# BusPirate-v5_0-SSOP.net
KiCad netlist of a schematic drawn in EAGLE
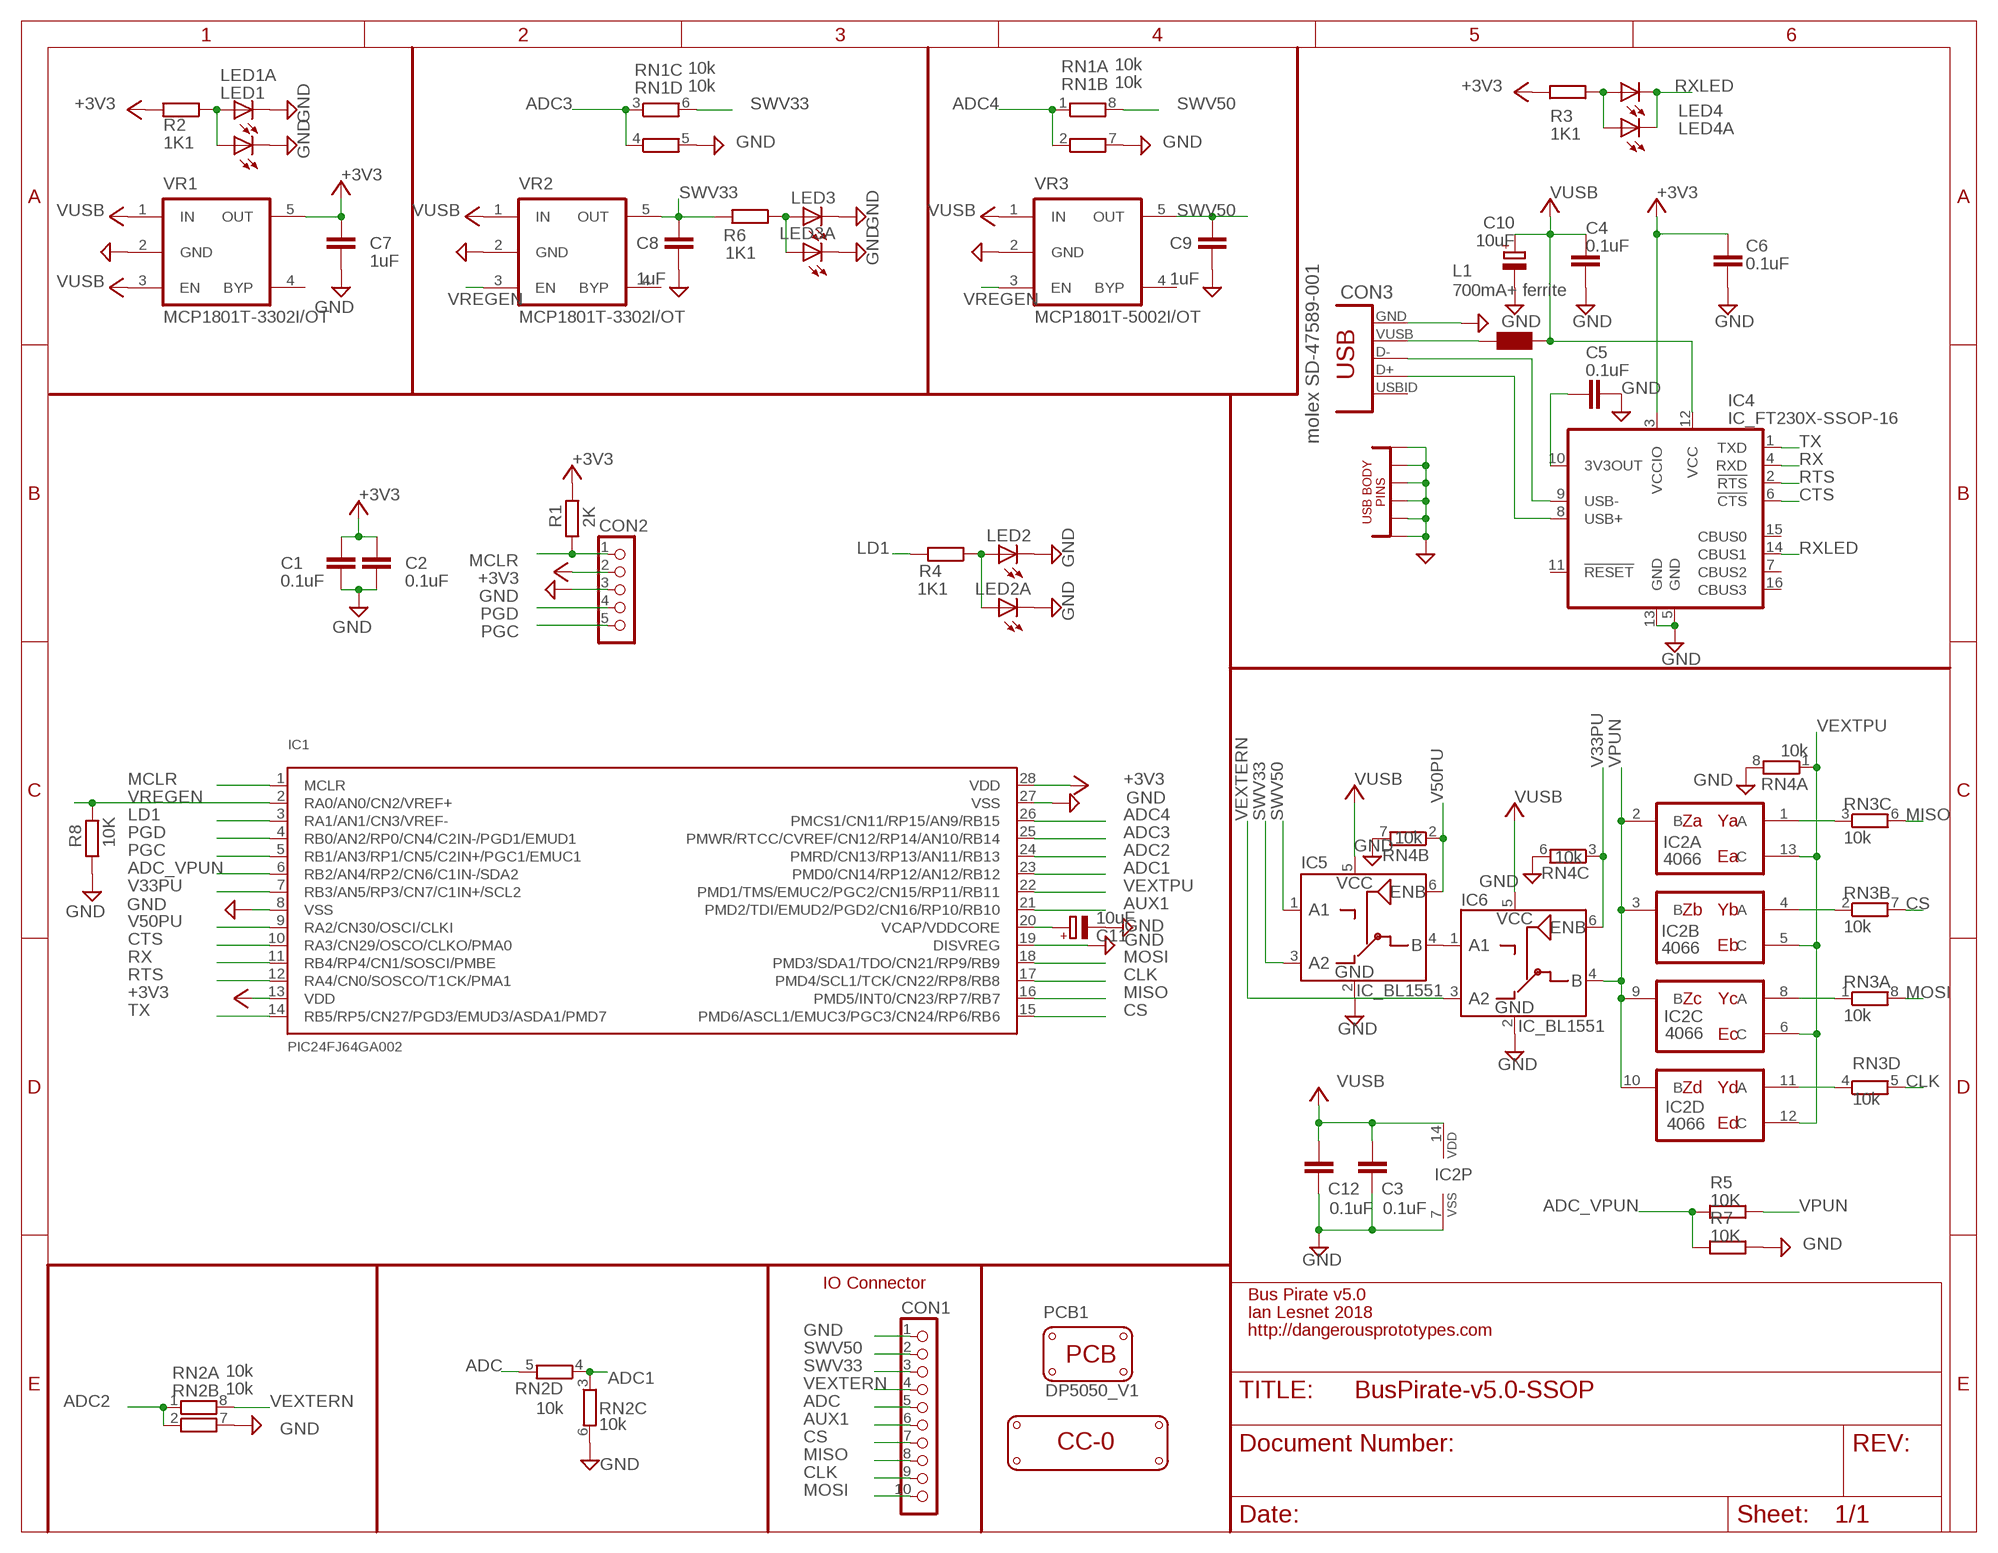
[diagram p0: schematic, sheet 1]

(export (version "E")
  (design (tool "Eeschema 10.0.6"))
  (components
    (comp (ref "C1")
      (value "0.1uF")
      (footprint "eagle-import:C603")
      (libsource (lib "eagle-import") (part "CAPC603"))
    )
    (comp (ref "C2")
      (value "0.1uF")
      (footprint "eagle-import:C603")
      (libsource (lib "eagle-import") (part "CAPC603"))
    )
    (comp (ref "C3")
      (value "0.1uF")
      (footprint "eagle-import:C603")
      (libsource (lib "eagle-import") (part "CAPC603"))
    )
    (comp (ref "C4")
      (value "0.1uF")
      (footprint "eagle-import:C603")
      (libsource (lib "eagle-import") (part "CAPC603"))
    )
    (comp (ref "C5")
      (value "0.1uF")
      (footprint "eagle-import:C603")
      (libsource (lib "eagle-import") (part "CAPC603"))
    )
    (comp (ref "C6")
      (value "0.1uF")
      (footprint "eagle-import:C603")
      (libsource (lib "eagle-import") (part "CAPC603"))
    )
    (comp (ref "C7")
      (value "1uF")
      (footprint "eagle-import:C603")
      (libsource (lib "eagle-import") (part "CAPC603"))
    )
    (comp (ref "C8")
      (value "1uF")
      (footprint "eagle-import:C603")
      (libsource (lib "eagle-import") (part "CAPC603"))
    )
    (comp (ref "C9")
      (value "1uF")
      (footprint "eagle-import:C603")
      (libsource (lib "eagle-import") (part "CAPC603"))
    )
    (comp (ref "C10")
      (value "10uF")
      (footprint "eagle-import:SMC_A")
      (libsource (lib "eagle-import") (part "CPOL-EUSMCA"))
    )
    (comp (ref "C11")
      (value "10uF")
      (footprint "eagle-import:SMC_A")
      (libsource (lib "eagle-import") (part "CPOL-EUSMCA"))
    )
    (comp (ref "C12")
      (value "0.1uF")
      (footprint "eagle-import:C603")
      (libsource (lib "eagle-import") (part "CAPC603"))
    )
    (comp (ref "CON1")
      (value "CON_HEADER_1X10-RIGHT_ANGLED_PTH_SHROUDED")
      (footprint "eagle-import:M1X10_MALE_RIGHT_ANGLES_PTH_SHROUDED")
      (libsource (lib "eagle-import") (part "CON_HEADER_1X10-RIGHT_ANGLED_PTH_SHROUDED"))
    )
    (comp (ref "CON2")
      (value "CON_HEADER_1X05-PTH")
      (footprint "eagle-import:M1X5")
      (libsource (lib "eagle-import") (part "CON_HEADER_1X05-PTH"))
    )
    (comp (ref "CON3")
      (value "molex SD-47589-001")
      (footprint "eagle-import:CON_USB_MICRO-B-2-SD-47589-001")
      (libsource (lib "eagle-import") (part "CON-USB-F-MICRO-B-2"))
    )
    (comp (ref "IC1")
      (value "PIC24FJ64GA002")
      (footprint "eagle-import:SSOP28")
      (libsource (lib "eagle-import") (part "PIC24FJ64GA002"))
    )
    (comp (ref "IC2")
      (value "4066")
      (footprint "eagle-import:TSSOP14")
      (libsource (lib "eagle-import") (part "4066"))
    )
    (comp (ref "IC4")
      (value "IC_FT230X-SSOP-16")
      (footprint "eagle-import:SSOP-16-FTDI")
      (libsource (lib "eagle-import") (part "IC_FT230X-SSOP-16"))
    )
    (comp (ref "IC5")
      (value "IC_BL1551")
      (footprint "eagle-import:SC-70-6")
      (libsource (lib "eagle-import") (part "IC_BL1551"))
    )
    (comp (ref "IC6")
      (value "IC_BL1551")
      (footprint "eagle-import:SC-70-6")
      (libsource (lib "eagle-import") (part "IC_BL1551"))
    )
    (comp (ref "L1")
      (value "700mA+ ferrite")
      (footprint "eagle-import:WE-KI_0805_B")
      (libsource (lib "eagle-import") (part "WE-KIL_0805"))
    )
    (comp (ref "LED1")
      (value "LED-0805")
      (footprint "eagle-import:LED-805")
      (libsource (lib "eagle-import") (part "LED-0805"))
    )
    (comp (ref "LED1A")
      (value "LED-0805")
      (footprint "eagle-import:LED-805")
      (libsource (lib "eagle-import") (part "LED-0805"))
    )
    (comp (ref "LED2")
      (value "LED-0805")
      (footprint "eagle-import:LED-805")
      (libsource (lib "eagle-import") (part "LED-0805"))
    )
    (comp (ref "LED2A")
      (value "LED-0805")
      (footprint "eagle-import:LED-805")
      (libsource (lib "eagle-import") (part "LED-0805"))
    )
    (comp (ref "LED3")
      (value "LED-0805")
      (footprint "eagle-import:LED-805")
      (libsource (lib "eagle-import") (part "LED-0805"))
    )
    (comp (ref "LED3A")
      (value "LED-0805")
      (footprint "eagle-import:LED-805")
      (libsource (lib "eagle-import") (part "LED-0805"))
    )
    (comp (ref "LED4")
      (value "LED-0805")
      (footprint "eagle-import:LED-805")
      (libsource (lib "eagle-import") (part "LED-0805"))
    )
    (comp (ref "LED4A")
      (value "LED-0805")
      (footprint "eagle-import:LED-805")
      (libsource (lib "eagle-import") (part "LED-0805"))
    )
    (comp (ref "LOGO1")
      (value "LOGO_CC-0")
      (footprint "eagle-import:LOGO_CC-0")
      (libsource (lib "eagle-import") (part "LOGO_CC-0"))
    )
    (comp (ref "PCB1")
      (value "PCB_DP_SQUARE-5X5")
      (footprint "eagle-import:DP5050_V1")
      (libsource (lib "eagle-import") (part "PCB_DP_SQUARE-5X5"))
    )
    (comp (ref "R1")
      (value "2K")
      (footprint "eagle-import:R603")
      (libsource (lib "eagle-import") (part "RESISTORR603"))
    )
    (comp (ref "R2")
      (value "1K1")
      (footprint "eagle-import:R603")
      (libsource (lib "eagle-import") (part "RESISTORR603"))
    )
    (comp (ref "R3")
      (value "1K1")
      (footprint "eagle-import:R603")
      (libsource (lib "eagle-import") (part "RESISTORR603"))
    )
    (comp (ref "R4")
      (value "1K1")
      (footprint "eagle-import:R603")
      (libsource (lib "eagle-import") (part "RESISTORR603"))
    )
    (comp (ref "R5")
      (value "10K")
      (footprint "eagle-import:R603")
      (libsource (lib "eagle-import") (part "RESISTORR603"))
    )
    (comp (ref "R6")
      (value "1K1")
      (footprint "eagle-import:R603")
      (libsource (lib "eagle-import") (part "RESISTORR603"))
    )
    (comp (ref "R7")
      (value "10K")
      (footprint "eagle-import:R603")
      (libsource (lib "eagle-import") (part "RESISTORR603"))
    )
    (comp (ref "R8")
      (value "10K")
      (footprint "eagle-import:R603")
      (libsource (lib "eagle-import") (part "RESISTORR603"))
    )
    (comp (ref "RN1")
      (value "10k")
      (footprint "eagle-import:RN8P-4R-CRA06S")
      (libsource (lib "eagle-import") (part "RNETWORK"))
    )
    (comp (ref "RN2")
      (value "10k")
      (footprint "eagle-import:RN8P-4R-CRA06S")
      (libsource (lib "eagle-import") (part "RNETWORK"))
    )
    (comp (ref "RN3")
      (value "10k")
      (footprint "eagle-import:RN8P-4R-CRA06S")
      (libsource (lib "eagle-import") (part "RNETWORK"))
    )
    (comp (ref "RN4")
      (value "10k")
      (footprint "eagle-import:RN8P-4R-CRA06S")
      (libsource (lib "eagle-import") (part "RNETWORK"))
    )
    (comp (ref "VR1")
      (value "MCP1801T-3302I/OT")
      (footprint "eagle-import:SOT-23-5")
      (libsource (lib "eagle-import") (part "MIC5205"))
    )
    (comp (ref "VR2")
      (value "MCP1801T-3302I/OT")
      (footprint "eagle-import:SOT-23-5")
      (libsource (lib "eagle-import") (part "MIC5205"))
    )
    (comp (ref "VR3")
      (value "MCP1801T-5002I/OT")
      (footprint "eagle-import:SOT-23-5")
      (libsource (lib "eagle-import") (part "MIC5205"))
    )
  )
  (nets
    (net (code "1") (name "/ADC") (class "Default")
      (node (ref "CON1") (pin "5") (pinfunction "5_5") (pintype "passive"))
      (node (ref "RN2") (pin "5") (pinfunction "2_5") (pintype "passive"))
    )
    (net (code "2") (name "/ADC1") (class "Default")
      (node (ref "IC1") (pin "23") (pinfunction "PMD0/CN14/RP12/AN12/RB12_23") (pintype "bidirectional"))
      (node (ref "RN2") (pin "3") (pinfunction "1_3") (pintype "passive"))
      (node (ref "RN2") (pin "4") (pinfunction "1_4") (pintype "passive"))
    )
    (net (code "3") (name "/ADC2") (class "Default")
      (node (ref "IC1") (pin "24") (pinfunction "PMRD/CN13/RP13/AN11/RB13_24") (pintype "bidirectional"))
      (node (ref "RN2") (pin "1") (pinfunction "1_1") (pintype "passive"))
      (node (ref "RN2") (pin "2") (pinfunction "1_2") (pintype "passive"))
    )
    (net (code "4") (name "/ADC3") (class "Default")
      (node (ref "IC1") (pin "25") (pinfunction "PMWR/RTCC/CVREF/CN12/RP14/AN10/RB14_25") (pintype "bidirectional"))
      (node (ref "RN1") (pin "3") (pinfunction "1_3") (pintype "passive"))
      (node (ref "RN1") (pin "4") (pinfunction "1_4") (pintype "passive"))
    )
    (net (code "5") (name "/ADC4") (class "Default")
      (node (ref "IC1") (pin "26") (pinfunction "PMCS1/CN11/RP15/AN9/RB15_26") (pintype "bidirectional"))
      (node (ref "RN1") (pin "1") (pinfunction "1_1") (pintype "passive"))
      (node (ref "RN1") (pin "2") (pinfunction "1_2") (pintype "passive"))
    )
    (net (code "6") (name "/ADC_VPUN") (class "Default")
      (node (ref "IC1") (pin "6") (pinfunction "RB2/AN4/RP2/CN6/C1IN-/SDA2_6") (pintype "bidirectional"))
      (node (ref "R5") (pin "2") (pinfunction "2_2") (pintype "passive"))
      (node (ref "R7") (pin "2") (pinfunction "2_2") (pintype "passive"))
    )
    (net (code "7") (name "/AUX1") (class "Default")
      (node (ref "CON1") (pin "6") (pinfunction "6_6") (pintype "passive"))
      (node (ref "IC1") (pin "21") (pinfunction "PMD2/TDI/EMUD2/PGD2/CN16/RP10/RB10_21") (pintype "bidirectional"))
    )
    (net (code "8") (name "/CLK") (class "Default")
      (node (ref "CON1") (pin "9") (pinfunction "9_9") (pintype "passive"))
      (node (ref "IC1") (pin "17") (pinfunction "PMD4/SCL1/TCK/CN22/RP8/RB8_17") (pintype "bidirectional"))
      (node (ref "RN3") (pin "5") (pinfunction "2_5") (pintype "passive"))
    )
    (net (code "9") (name "/CS") (class "Default")
      (node (ref "CON1") (pin "7") (pinfunction "7_7") (pintype "passive"))
      (node (ref "IC1") (pin "15") (pinfunction "PMD6/ASCL1/EMUC3/PGC3/CN24/RP6/RB6_15") (pintype "bidirectional"))
      (node (ref "RN3") (pin "7") (pinfunction "2_7") (pintype "passive"))
    )
    (net (code "10") (name "/CTS") (class "Default")
      (node (ref "IC1") (pin "10") (pinfunction "RA3/CN29/OSCO/CLKO/PMA0_10") (pintype "bidirectional"))
      (node (ref "IC4") (pin "6") (pinfunction "~{CTS}_6") (pintype "bidirectional"))
    )
    (net (code "11") (name "/LD1") (class "Default")
      (node (ref "IC1") (pin "3") (pinfunction "RA1/AN1/CN3/VREF-_3") (pintype "bidirectional"))
      (node (ref "R4") (pin "2") (pinfunction "2_2") (pintype "passive"))
    )
    (net (code "12") (name "/MCLR") (class "Default")
      (node (ref "CON2") (pin "1") (pinfunction "1_1") (pintype "bidirectional"))
      (node (ref "IC1") (pin "1") (pinfunction "MCLR_1") (pintype "input"))
      (node (ref "R1") (pin "1") (pinfunction "1_1") (pintype "passive"))
    )
    (net (code "13") (name "/MISO") (class "Default")
      (node (ref "CON1") (pin "8") (pinfunction "8_8") (pintype "passive"))
      (node (ref "IC1") (pin "16") (pinfunction "PMD5/INT0/CN23/RP7/RB7_16") (pintype "bidirectional"))
      (node (ref "RN3") (pin "6") (pinfunction "2_6") (pintype "passive"))
    )
    (net (code "14") (name "/MOSI") (class "Default")
      (node (ref "CON1") (pin "10") (pinfunction "10_10") (pintype "passive"))
      (node (ref "IC1") (pin "18") (pinfunction "PMD3/SDA1/TDO/CN21/RP9/RB9_18") (pintype "bidirectional"))
      (node (ref "RN3") (pin "8") (pinfunction "2_8") (pintype "passive"))
    )
    (net (code "15") (name "/PGC") (class "Default")
      (node (ref "CON2") (pin "5") (pinfunction "5_5") (pintype "bidirectional"))
      (node (ref "IC1") (pin "5") (pinfunction "RB1/AN3/RP1/CN5/C2IN+/PGC1/EMUC1_5") (pintype "bidirectional"))
    )
    (net (code "16") (name "/PGD") (class "Default")
      (node (ref "CON2") (pin "4") (pinfunction "4_4") (pintype "bidirectional"))
      (node (ref "IC1") (pin "4") (pinfunction "RB0/AN2/RP0/CN4/C2IN-/PGD1/EMUD1_4") (pintype "bidirectional"))
    )
    (net (code "17") (name "/RTS") (class "Default")
      (node (ref "IC1") (pin "12") (pinfunction "RA4/CN0/SOSCO/T1CK/PMA1_12") (pintype "bidirectional"))
      (node (ref "IC4") (pin "2") (pinfunction "~{RTS}_2") (pintype "bidirectional"))
    )
    (net (code "18") (name "/RX") (class "Default")
      (node (ref "IC1") (pin "11") (pinfunction "RB4/RP4/CN1/SOSCI/PMBE_11") (pintype "bidirectional"))
      (node (ref "IC4") (pin "4") (pinfunction "RXD_4") (pintype "input"))
    )
    (net (code "19") (name "/RXLED") (class "Default")
      (node (ref "IC4") (pin "14") (pinfunction "CBUS1_14") (pintype "bidirectional"))
      (node (ref "LED4") (pin "C") (pinfunction "C_C") (pintype "passive"))
      (node (ref "LED4A") (pin "C") (pinfunction "C_C") (pintype "passive"))
    )
    (net (code "20") (name "/SWV33") (class "Default")
      (node (ref "C8") (pin "1") (pinfunction "1_1") (pintype "passive"))
      (node (ref "CON1") (pin "3") (pinfunction "3_3") (pintype "passive"))
      (node (ref "IC5") (pin "3") (pinfunction "A2_3") (pintype "input"))
      (node (ref "R6") (pin "2") (pinfunction "2_2") (pintype "passive"))
      (node (ref "RN1") (pin "6") (pinfunction "2_6") (pintype "passive"))
      (node (ref "VR2") (pin "5") (pinfunction "OUT_5") (pintype "bidirectional"))
    )
    (net (code "21") (name "/SWV50") (class "Default")
      (node (ref "C9") (pin "1") (pinfunction "1_1") (pintype "passive"))
      (node (ref "CON1") (pin "2") (pinfunction "2_2") (pintype "passive"))
      (node (ref "IC5") (pin "1") (pinfunction "A1_1") (pintype "input"))
      (node (ref "RN1") (pin "8") (pinfunction "2_8") (pintype "passive"))
      (node (ref "VR3") (pin "5") (pinfunction "OUT_5") (pintype "bidirectional"))
    )
    (net (code "22") (name "/TX") (class "Default")
      (node (ref "IC1") (pin "14") (pinfunction "RB5/RP5/CN27/PGD3/EMUD3/ASDA1/PMD7_14") (pintype "bidirectional"))
      (node (ref "IC4") (pin "1") (pinfunction "TXD_1") (pintype "output"))
    )
    (net (code "23") (name "/V33PU") (class "Default")
      (node (ref "IC1") (pin "7") (pinfunction "RB3/AN5/RP3/CN7/C1IN+/SCL2_7") (pintype "bidirectional"))
      (node (ref "IC6") (pin "6") (pinfunction "ENB_6") (pintype "input"))
      (node (ref "RN4") (pin "3") (pinfunction "1_3") (pintype "passive"))
    )
    (net (code "24") (name "/V50PU") (class "Default")
      (node (ref "IC1") (pin "9") (pinfunction "RA2/CN30/OSCI/CLKI_9") (pintype "bidirectional"))
      (node (ref "IC5") (pin "6") (pinfunction "ENB_6") (pintype "input"))
      (node (ref "RN4") (pin "2") (pinfunction "1_2") (pintype "passive"))
    )
    (net (code "25") (name "/VEXTERN") (class "Default")
      (node (ref "CON1") (pin "4") (pinfunction "4_4") (pintype "passive"))
      (node (ref "IC6") (pin "3") (pinfunction "A2_3") (pintype "input"))
      (node (ref "RN2") (pin "8") (pinfunction "2_8") (pintype "passive"))
    )
    (net (code "26") (name "/VEXTPU") (class "Default")
      (node (ref "IC1") (pin "22") (pinfunction "PMD1/TMS/EMUC2/PGC2/CN15/RP11/RB11_22") (pintype "bidirectional"))
      (node (ref "IC2") (pin "12") (pinfunction "C_12") (pintype "input"))
      (node (ref "IC2") (pin "13") (pinfunction "C_13") (pintype "input"))
      (node (ref "IC2") (pin "5") (pinfunction "C_5") (pintype "input"))
      (node (ref "IC2") (pin "6") (pinfunction "C_6") (pintype "input"))
      (node (ref "RN4") (pin "1") (pinfunction "1_1") (pintype "passive"))
    )
    (net (code "27") (name "/VPUN") (class "Default")
      (node (ref "IC2") (pin "10") (pinfunction "B_10") (pintype "tri_state"))
      (node (ref "IC2") (pin "2") (pinfunction "B_2") (pintype "tri_state"))
      (node (ref "IC2") (pin "3") (pinfunction "B_3") (pintype "tri_state"))
      (node (ref "IC2") (pin "9") (pinfunction "B_9") (pintype "tri_state"))
      (node (ref "IC6") (pin "4") (pinfunction "B_4") (pintype "output"))
      (node (ref "R5") (pin "1") (pinfunction "1_1") (pintype "passive"))
    )
    (net (code "28") (name "/VREGEN") (class "Default")
      (node (ref "IC1") (pin "2") (pinfunction "RA0/AN0/CN2/VREF+_2") (pintype "bidirectional"))
      (node (ref "R8") (pin "2") (pinfunction "2_2") (pintype "passive"))
      (node (ref "VR2") (pin "3") (pinfunction "EN_3") (pintype "bidirectional"))
      (node (ref "VR3") (pin "3") (pinfunction "EN_3") (pintype "bidirectional"))
    )
    (net (code "29") (name "GND") (class "Default")
      (node (ref "C1") (pin "2") (pinfunction "2_2") (pintype "passive"))
      (node (ref "C10") (pin "-") (pinfunction "-_-") (pintype "passive"))
      (node (ref "C11") (pin "-") (pinfunction "-_-") (pintype "passive"))
      (node (ref "C12") (pin "2") (pinfunction "2_2") (pintype "passive"))
      (node (ref "C2") (pin "2") (pinfunction "2_2") (pintype "passive"))
      (node (ref "C3") (pin "2") (pinfunction "2_2") (pintype "passive"))
      (node (ref "C4") (pin "2") (pinfunction "2_2") (pintype "passive"))
      (node (ref "C5") (pin "2") (pinfunction "2_2") (pintype "passive"))
      (node (ref "C6") (pin "2") (pinfunction "2_2") (pintype "passive"))
      (node (ref "C7") (pin "2") (pinfunction "2_2") (pintype "passive"))
      (node (ref "C8") (pin "2") (pinfunction "2_2") (pintype "passive"))
      (node (ref "C9") (pin "2") (pinfunction "2_2") (pintype "passive"))
      (node (ref "CON1") (pin "1") (pinfunction "1_1") (pintype "passive"))
      (node (ref "CON2") (pin "3") (pinfunction "3_3") (pintype "bidirectional"))
      (node (ref "CON3") (pin "BODY@1") (pinfunction "P$1_BODY@1") (pintype "passive"))
      (node (ref "CON3") (pin "BODY@10") (pinfunction "P$6_BODY@10") (pintype "passive"))
      (node (ref "CON3") (pin "BODY@2") (pinfunction "P$1_BODY@2") (pintype "passive"))
      (node (ref "CON3") (pin "BODY@3") (pinfunction "P$2_BODY@3") (pintype "passive"))
      (node (ref "CON3") (pin "BODY@4") (pinfunction "P$2_BODY@4") (pintype "passive"))
      (node (ref "CON3") (pin "BODY@5") (pinfunction "P$3_BODY@5") (pintype "passive"))
      (node (ref "CON3") (pin "BODY@6") (pinfunction "P$3_BODY@6") (pintype "passive"))
      (node (ref "CON3") (pin "BODY@7") (pinfunction "P$4_BODY@7") (pintype "passive"))
      (node (ref "CON3") (pin "BODY@8") (pinfunction "P$5_BODY@8") (pintype "passive"))
      (node (ref "CON3") (pin "BODY@9") (pinfunction "P$6_BODY@9") (pintype "passive"))
      (node (ref "CON3") (pin "P5") (pinfunction "GND_P5") (pintype "bidirectional"))
      (node (ref "IC1") (pin "19") (pinfunction "DISVREG_19") (pintype "power_in"))
      (node (ref "IC1") (pin "27") (pinfunction "VSS_27") (pintype "power_in"))
      (node (ref "IC1") (pin "8") (pinfunction "VSS_8") (pintype "power_in"))
      (node (ref "IC2") (pin "7") (pinfunction "VSS_7") (pintype "power_in"))
      (node (ref "IC4") (pin "13") (pinfunction "GND_13") (pintype "power_in"))
      (node (ref "IC4") (pin "5") (pinfunction "GND_5") (pintype "power_in"))
      (node (ref "IC5") (pin "2") (pinfunction "GND_2") (pintype "power_in"))
      (node (ref "IC6") (pin "2") (pinfunction "GND_2") (pintype "power_in"))
      (node (ref "LED1") (pin "C") (pinfunction "C_C") (pintype "passive"))
      (node (ref "LED1A") (pin "C") (pinfunction "C_C") (pintype "passive"))
      (node (ref "LED2") (pin "C") (pinfunction "C_C") (pintype "passive"))
      (node (ref "LED2A") (pin "C") (pinfunction "C_C") (pintype "passive"))
      (node (ref "LED3") (pin "C") (pinfunction "C_C") (pintype "passive"))
      (node (ref "LED3A") (pin "C") (pinfunction "C_C") (pintype "passive"))
      (node (ref "R7") (pin "1") (pinfunction "1_1") (pintype "passive"))
      (node (ref "R8") (pin "1") (pinfunction "1_1") (pintype "passive"))
      (node (ref "RN1") (pin "5") (pinfunction "2_5") (pintype "passive"))
      (node (ref "RN1") (pin "7") (pinfunction "2_7") (pintype "passive"))
      (node (ref "RN2") (pin "6") (pinfunction "2_6") (pintype "passive"))
      (node (ref "RN2") (pin "7") (pinfunction "2_7") (pintype "passive"))
      (node (ref "RN4") (pin "6") (pinfunction "2_6") (pintype "passive"))
      (node (ref "RN4") (pin "7") (pinfunction "2_7") (pintype "passive"))
      (node (ref "RN4") (pin "8") (pinfunction "2_8") (pintype "passive"))
      (node (ref "VR1") (pin "2") (pinfunction "GND_2") (pintype "bidirectional"))
      (node (ref "VR2") (pin "2") (pinfunction "GND_2") (pintype "bidirectional"))
      (node (ref "VR3") (pin "2") (pinfunction "GND_2") (pintype "bidirectional"))
    )
    (net (code "30") (name "Net-(CON3B-D+)") (class "Default")
      (node (ref "CON3") (pin "P3") (pinfunction "D+_P3") (pintype "bidirectional"))
      (node (ref "IC4") (pin "8") (pinfunction "USB+_8") (pintype "output"))
    )
    (net (code "31") (name "Net-(CON3B-D-)") (class "Default")
      (node (ref "CON3") (pin "P2") (pinfunction "D-_P2") (pintype "bidirectional"))
      (node (ref "IC4") (pin "9") (pinfunction "USB-_9") (pintype "input"))
    )
    (net (code "32") (name "Net-(CON3B-VUSB)") (class "Default")
      (node (ref "CON3") (pin "P1") (pinfunction "VUSB_P1") (pintype "bidirectional"))
      (node (ref "L1") (pin "2") (pinfunction "1_2") (pintype "passive"))
    )
    (net (code "33") (name "Net-(IC1-VCAP{slash}VDDCORE)") (class "Default")
      (node (ref "C11") (pin "+") (pinfunction "+_+") (pintype "passive"))
      (node (ref "IC1") (pin "20") (pinfunction "VCAP/VDDCORE_20") (pintype "power_in"))
    )
    (net (code "34") (name "Net-(IC2A-A)") (class "Default")
      (node (ref "IC2") (pin "1") (pinfunction "A_1") (pintype "tri_state"))
      (node (ref "RN3") (pin "3") (pinfunction "1_3") (pintype "passive"))
    )
    (net (code "35") (name "Net-(IC2B-A)") (class "Default")
      (node (ref "IC2") (pin "4") (pinfunction "A_4") (pintype "tri_state"))
      (node (ref "RN3") (pin "2") (pinfunction "1_2") (pintype "passive"))
    )
    (net (code "36") (name "Net-(IC2C-A)") (class "Default")
      (node (ref "IC2") (pin "8") (pinfunction "A_8") (pintype "tri_state"))
      (node (ref "RN3") (pin "1") (pinfunction "1_1") (pintype "passive"))
    )
    (net (code "37") (name "Net-(IC2D-A)") (class "Default")
      (node (ref "IC2") (pin "11") (pinfunction "A_11") (pintype "tri_state"))
      (node (ref "RN3") (pin "4") (pinfunction "1_4") (pintype "passive"))
    )
    (net (code "38") (name "Net-(IC4-3V3OUT)") (class "Default")
      (node (ref "C5") (pin "1") (pinfunction "1_1") (pintype "passive"))
      (node (ref "IC4") (pin "10") (pinfunction "3V3OUT_10") (pintype "power_in"))
    )
    (net (code "39") (name "Net-(IC5-B)") (class "Default")
      (node (ref "IC5") (pin "4") (pinfunction "B_4") (pintype "output"))
      (node (ref "IC6") (pin "1") (pinfunction "A1_1") (pintype "input"))
    )
    (net (code "40") (name "Net-(LED1-PadA)") (class "Default")
      (node (ref "LED1") (pin "A") (pinfunction "A_A") (pintype "passive"))
      (node (ref "LED1A") (pin "A") (pinfunction "A_A") (pintype "passive"))
      (node (ref "R2") (pin "1") (pinfunction "1_1") (pintype "passive"))
    )
    (net (code "41") (name "Net-(LED2-PadA)") (class "Default")
      (node (ref "LED2") (pin "A") (pinfunction "A_A") (pintype "passive"))
      (node (ref "LED2A") (pin "A") (pinfunction "A_A") (pintype "passive"))
      (node (ref "R4") (pin "1") (pinfunction "1_1") (pintype "passive"))
    )
    (net (code "42") (name "Net-(LED3-PadA)") (class "Default")
      (node (ref "LED3") (pin "A") (pinfunction "A_A") (pintype "passive"))
      (node (ref "LED3A") (pin "A") (pinfunction "A_A") (pintype "passive"))
      (node (ref "R6") (pin "1") (pinfunction "1_1") (pintype "passive"))
    )
    (net (code "43") (name "Net-(LED4-PadA)") (class "Default")
      (node (ref "LED4") (pin "A") (pinfunction "A_A") (pintype "passive"))
      (node (ref "LED4A") (pin "A") (pinfunction "A_A") (pintype "passive"))
      (node (ref "R3") (pin "1") (pinfunction "1_1") (pintype "passive"))
    )
    (net (code "44") (name "SUPPLY_+3V3") (class "Default")
      (node (ref "C1") (pin "1") (pinfunction "1_1") (pintype "passive"))
      (node (ref "C2") (pin "1") (pinfunction "1_1") (pintype "passive"))
      (node (ref "C6") (pin "1") (pinfunction "1_1") (pintype "passive"))
      (node (ref "C7") (pin "1") (pinfunction "1_1") (pintype "passive"))
      (node (ref "CON2") (pin "2") (pinfunction "2_2") (pintype "bidirectional"))
      (node (ref "IC1") (pin "13") (pinfunction "VDD_13") (pintype "power_in"))
      (node (ref "IC1") (pin "28") (pinfunction "VDD_28") (pintype "power_in"))
      (node (ref "IC4") (pin "3") (pinfunction "VCCIO_3") (pintype "power_in"))
      (node (ref "R1") (pin "2") (pinfunction "2_2") (pintype "passive"))
      (node (ref "R2") (pin "2") (pinfunction "2_2") (pintype "passive"))
      (node (ref "R3") (pin "2") (pinfunction "2_2") (pintype "passive"))
      (node (ref "VR1") (pin "5") (pinfunction "OUT_5") (pintype "bidirectional"))
    )
    (net (code "45") (name "SUPPLY_VUSB") (class "Default")
      (node (ref "C10") (pin "+") (pinfunction "+_+") (pintype "passive"))
      (node (ref "C12") (pin "1") (pinfunction "1_1") (pintype "passive"))
      (node (ref "C3") (pin "1") (pinfunction "1_1") (pintype "passive"))
      (node (ref "C4") (pin "1") (pinfunction "1_1") (pintype "passive"))
      (node (ref "IC2") (pin "14") (pinfunction "VDD_14") (pintype "power_in"))
      (node (ref "IC4") (pin "12") (pinfunction "VCC_12") (pintype "power_in"))
      (node (ref "IC5") (pin "5") (pinfunction "VCC_5") (pintype "power_in"))
      (node (ref "IC6") (pin "5") (pinfunction "VCC_5") (pintype "power_in"))
      (node (ref "L1") (pin "1") (pinfunction "2_1") (pintype "passive"))
      (node (ref "VR1") (pin "1") (pinfunction "IN_1") (pintype "bidirectional"))
      (node (ref "VR1") (pin "3") (pinfunction "EN_3") (pintype "bidirectional"))
      (node (ref "VR2") (pin "1") (pinfunction "IN_1") (pintype "bidirectional"))
      (node (ref "VR3") (pin "1") (pinfunction "IN_1") (pintype "bidirectional"))
    )
    (net (code "46") (name "unconnected-(CON3B-USBID-PadP4)") (class "Default")
      (node (ref "CON3") (pin "P4") (pinfunction "USBID_P4") (pintype "bidirectional"))
    )
    (net (code "47") (name "unconnected-(IC4-CBUS0-Pad15)") (class "Default")
      (node (ref "IC4") (pin "15") (pinfunction "CBUS0_15") (pintype "bidirectional"))
    )
    (net (code "48") (name "unconnected-(IC4-CBUS2-Pad7)") (class "Default")
      (node (ref "IC4") (pin "7") (pinfunction "CBUS2_7") (pintype "bidirectional"))
    )
    (net (code "49") (name "unconnected-(IC4-CBUS3-Pad16)") (class "Default")
      (node (ref "IC4") (pin "16") (pinfunction "CBUS3_16") (pintype "bidirectional"))
    )
    (net (code "50") (name "unconnected-(IC4-~{RESET}-Pad11)") (class "Default")
      (node (ref "IC4") (pin "11") (pinfunction "~{RESET}_11") (pintype "bidirectional"))
    )
    (net (code "51") (name "unconnected-(VR1-BYP-Pad4)") (class "Default")
      (node (ref "VR1") (pin "4") (pinfunction "BYP_4") (pintype "bidirectional"))
    )
    (net (code "52") (name "unconnected-(VR2-BYP-Pad4)") (class "Default")
      (node (ref "VR2") (pin "4") (pinfunction "BYP_4") (pintype "bidirectional"))
    )
    (net (code "53") (name "unconnected-(VR3-BYP-Pad4)") (class "Default")
      (node (ref "VR3") (pin "4") (pinfunction "BYP_4") (pintype "bidirectional"))
    )
  )
)
